# respi.net
KiCad netlist of a schematic drawn in Altium Designer
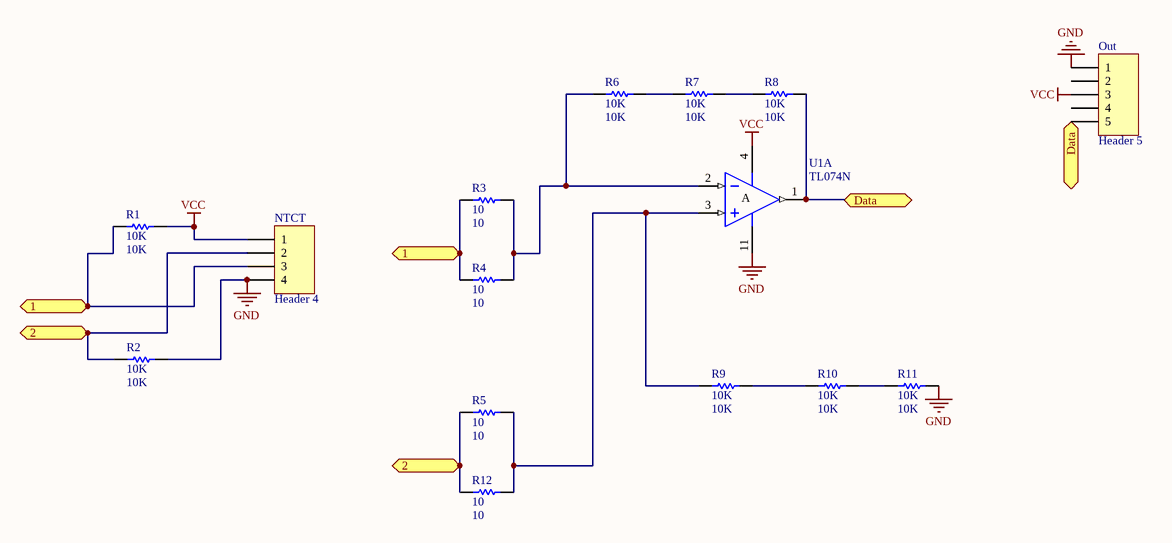
[diagram p0: respi.SchDoc]

(export (version "E")
  (design (tool "Eeschema 10.0.6"))
  (components
    (comp (ref "NTCT")
      (value "Header 4")
      (footprint "HDR1X4")
      (description "Header, 4-Pin")
      (fields (field (name "PUBLISHER") "Altium Limited"))
      (libsource (lib "Miscellaneous Connectors") (part "Header 4"))
    )
    (comp (ref "Out")
      (value "Header 5")
      (footprint "HDR1X5")
      (description "Header, 5-Pin")
      (fields (field (name "PUBLISHER") "Altium Limited"))
      (libsource (lib "Miscellaneous Connectors") (part "Header 5"))
    )
    (comp (ref "R1")
      (value "10K")
      (footprint "AXIAL-0.3")
      (description "Resistor")
      (fields (field (name "ALTIUM_VALUE") "10K") (field (name "PUBLISHER") "Altium Limited"))
      (libsource (lib "Miscellaneous Devices") (part "Res1"))
    )
    (comp (ref "R2")
      (value "10K")
      (footprint "AXIAL-0.3")
      (description "Resistor")
      (fields (field (name "ALTIUM_VALUE") "10K") (field (name "PUBLISHER") "Altium Limited"))
      (libsource (lib "Miscellaneous Devices") (part "Res1"))
    )
    (comp (ref "R3")
      (value "10")
      (footprint "AXIAL-0.3")
      (description "Resistor")
      (fields (field (name "ALTIUM_VALUE") "10") (field (name "PUBLISHER") "Altium Limited"))
      (libsource (lib "Miscellaneous Devices") (part "Res1"))
    )
    (comp (ref "R4")
      (value "10")
      (footprint "AXIAL-0.3")
      (description "Resistor")
      (fields (field (name "ALTIUM_VALUE") "10") (field (name "PUBLISHER") "Altium Limited"))
      (libsource (lib "Miscellaneous Devices") (part "Res1"))
    )
    (comp (ref "R5")
      (value "10")
      (footprint "AXIAL-0.3")
      (description "Resistor")
      (fields (field (name "ALTIUM_VALUE") "10") (field (name "PUBLISHER") "Altium Limited"))
      (libsource (lib "Miscellaneous Devices") (part "Res1"))
    )
    (comp (ref "R6")
      (value "10K")
      (footprint "AXIAL-0.3")
      (description "Resistor")
      (fields (field (name "ALTIUM_VALUE") "10K") (field (name "PUBLISHER") "Altium Limited"))
      (libsource (lib "Miscellaneous Devices") (part "Res1"))
    )
    (comp (ref "R7")
      (value "10K")
      (footprint "AXIAL-0.3")
      (description "Resistor")
      (fields (field (name "ALTIUM_VALUE") "10K") (field (name "PUBLISHER") "Altium Limited"))
      (libsource (lib "Miscellaneous Devices") (part "Res1"))
    )
    (comp (ref "R8")
      (value "10K")
      (footprint "AXIAL-0.3")
      (description "Resistor")
      (fields (field (name "ALTIUM_VALUE") "10K") (field (name "PUBLISHER") "Altium Limited"))
      (libsource (lib "Miscellaneous Devices") (part "Res1"))
    )
    (comp (ref "R9")
      (value "10K")
      (footprint "AXIAL-0.3")
      (description "Resistor")
      (fields (field (name "ALTIUM_VALUE") "10K") (field (name "PUBLISHER") "Altium Limited"))
      (libsource (lib "Miscellaneous Devices") (part "Res1"))
    )
    (comp (ref "R10")
      (value "10K")
      (footprint "AXIAL-0.3")
      (description "Resistor")
      (fields (field (name "ALTIUM_VALUE") "10K") (field (name "PUBLISHER") "Altium Limited"))
      (libsource (lib "Miscellaneous Devices") (part "Res1"))
    )
    (comp (ref "R11")
      (value "10K")
      (footprint "AXIAL-0.3")
      (description "Resistor")
      (fields (field (name "ALTIUM_VALUE") "10K") (field (name "PUBLISHER") "Altium Limited"))
      (libsource (lib "Miscellaneous Devices") (part "Res1"))
    )
    (comp (ref "R12")
      (value "10")
      (footprint "AXIAL-0.3")
      (description "Resistor")
      (fields (field (name "ALTIUM_VALUE") "10") (field (name "PUBLISHER") "Altium Limited"))
      (libsource (lib "Miscellaneous Devices") (part "Res1"))
    )
    (comp (ref "U1")
      (value "TL074N")
      (footprint "N014")
      (description "Low-Noise JFET-Input Operational Amplifier")
      (fields (field (name "PUBLISHER") "Altium Limited"))
      (libsource (lib "TI Operational Amplifier") (part "TL074N"))
    )
  )
  (nets
    (net (code "1") (name "/1") (class "Default")
      (node (ref "NTCT") (pin "3") (pinfunction "3_3") (pintype "passive"))
      (node (ref "R1") (pin "1") (pinfunction "1_1") (pintype "passive"))
      (node (ref "R3") (pin "1") (pinfunction "1_1") (pintype "passive"))
      (node (ref "R4") (pin "1") (pinfunction "1_1") (pintype "passive"))
    )
    (net (code "2") (name "/2") (class "Default")
      (node (ref "NTCT") (pin "2") (pinfunction "2_2") (pintype "passive"))
      (node (ref "R12") (pin "1") (pinfunction "1_1") (pintype "passive"))
      (node (ref "R2") (pin "1") (pinfunction "1_1") (pintype "passive"))
      (node (ref "R5") (pin "1") (pinfunction "1_1") (pintype "passive"))
    )
    (net (code "3") (name "/Data") (class "Default")
      (node (ref "Out") (pin "5") (pinfunction "5_5") (pintype "passive"))
      (node (ref "R8") (pin "2") (pinfunction "2_2") (pintype "passive"))
      (node (ref "U1") (pin "1") (pinfunction "OUT_1") (pintype "output"))
    )
    (net (code "4") (name "GND") (class "Default")
      (node (ref "NTCT") (pin "4") (pinfunction "4_4") (pintype "passive"))
      (node (ref "Out") (pin "1") (pinfunction "1_1") (pintype "passive"))
      (node (ref "R11") (pin "2") (pinfunction "2_2") (pintype "passive"))
      (node (ref "R2") (pin "2") (pinfunction "2_2") (pintype "passive"))
      (node (ref "U1") (pin "11") (pinfunction "V-_11") (pintype "power_in"))
    )
    (net (code "5") (name "Net-(R6-Pad2)") (class "Default")
      (node (ref "R6") (pin "2") (pinfunction "2_2") (pintype "passive"))
      (node (ref "R7") (pin "1") (pinfunction "1_1") (pintype "passive"))
    )
    (net (code "6") (name "Net-(R7-Pad2)") (class "Default")
      (node (ref "R7") (pin "2") (pinfunction "2_2") (pintype "passive"))
      (node (ref "R8") (pin "1") (pinfunction "1_1") (pintype "passive"))
    )
    (net (code "7") (name "Net-(R10-Pad1)") (class "Default")
      (node (ref "R10") (pin "1") (pinfunction "1_1") (pintype "passive"))
      (node (ref "R9") (pin "2") (pinfunction "2_2") (pintype "passive"))
    )
    (net (code "8") (name "Net-(R10-Pad2)") (class "Default")
      (node (ref "R10") (pin "2") (pinfunction "2_2") (pintype "passive"))
      (node (ref "R11") (pin "1") (pinfunction "1_1") (pintype "passive"))
    )
    (net (code "9") (name "Net-(U1A-IN+)") (class "Default")
      (node (ref "R12") (pin "2") (pinfunction "2_2") (pintype "passive"))
      (node (ref "R5") (pin "2") (pinfunction "2_2") (pintype "passive"))
      (node (ref "R9") (pin "1") (pinfunction "1_1") (pintype "passive"))
      (node (ref "U1") (pin "3") (pinfunction "IN+_3") (pintype "input"))
    )
    (net (code "10") (name "Net-(U1A-IN-)") (class "Default")
      (node (ref "R3") (pin "2") (pinfunction "2_2") (pintype "passive"))
      (node (ref "R4") (pin "2") (pinfunction "2_2") (pintype "passive"))
      (node (ref "R6") (pin "1") (pinfunction "1_1") (pintype "passive"))
      (node (ref "U1") (pin "2") (pinfunction "IN-_2") (pintype "input"))
    )
    (net (code "11") (name "VCC") (class "Default")
      (node (ref "NTCT") (pin "1") (pinfunction "1_1") (pintype "passive"))
      (node (ref "Out") (pin "3") (pinfunction "3_3") (pintype "passive"))
      (node (ref "R1") (pin "2") (pinfunction "2_2") (pintype "passive"))
      (node (ref "U1") (pin "4") (pinfunction "V+_4") (pintype "power_in"))
    )
    (net (code "12") (name "unconnected-(Out-Pad2)") (class "Default")
      (node (ref "Out") (pin "2") (pinfunction "2_2") (pintype "passive"))
    )
    (net (code "13") (name "unconnected-(Out-Pad4)") (class "Default")
      (node (ref "Out") (pin "4") (pinfunction "4_4") (pintype "passive"))
    )
  )
)
